# Smart_Extruder_Board.net
KiCad netlist of a schematic drawn in EAGLE
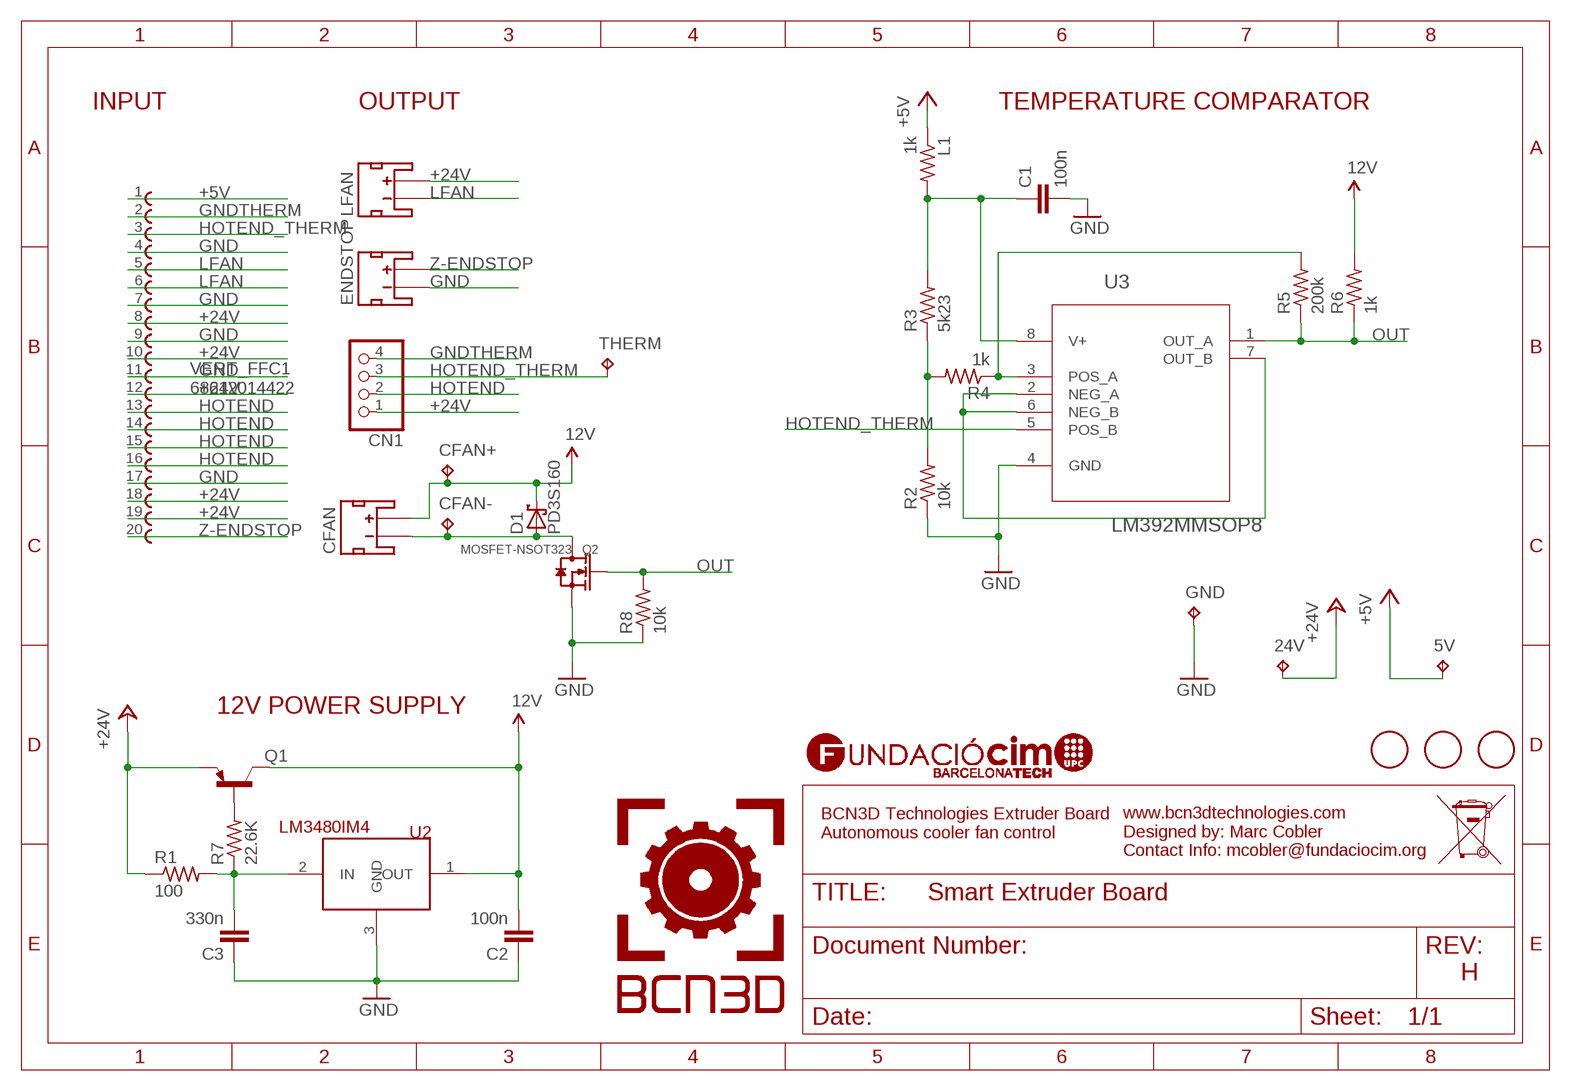
[diagram p0: schematic, sheet 1]

(export (version "E")
  (design (tool "Eeschema 10.0.6"))
  (components
    (comp (ref "5V")
      (value "TPB1,27")
      (footprint "eagle-import:B1,27")
      (libsource (lib "eagle-import") (part "TPB1,27"))
    )
    (comp (ref "24V")
      (value "TPB1,27")
      (footprint "eagle-import:B1,27")
      (libsource (lib "eagle-import") (part "TPB1,27"))
    )
    (comp (ref "C1")
      (value "100n")
      (footprint "eagle-import:C0603K")
      (fields (field (name "MF") "AVX") (field (name "MPN") "06035C104KAT2A"))
      (libsource (lib "eagle-import") (part "C-EUC0603K"))
    )
    (comp (ref "C2")
      (value "100n")
      (footprint "eagle-import:C0603K")
      (fields (field (name "MF") "AVX") (field (name "MPN") "06035C104KAT2A"))
      (libsource (lib "eagle-import") (part "C-EUC0603K"))
    )
    (comp (ref "C3")
      (value "330n")
      (footprint "eagle-import:C0805")
      (fields (field (name "MF") "MURATA") (field (name "MPN") "GRM219R71H334KA88D"))
      (libsource (lib "eagle-import") (part "C-EUC0805"))
    )
    (comp (ref "CFAN")
      (value "JST_2MM_MALE")
      (footprint "eagle-import:JST-2-SMD")
      (fields
        (field (name "MF") "JST (JAPAN SOLDERLESS TERMINALS)")
        (field (name "MPN") "S2B-PH-SM4-TB(LF)(SN)")
      )
      (libsource (lib "eagle-import") (part "JST_2MM_MALE"))
    )
    (comp (ref "CFAN+")
      (value "TPB1,27")
      (footprint "eagle-import:B1,27")
      (libsource (lib "eagle-import") (part "TPB1,27"))
    )
    (comp (ref "CFAN-")
      (value "TPB1,27")
      (footprint "eagle-import:B1,27")
      (libsource (lib "eagle-import") (part "TPB1,27"))
    )
    (comp (ref "CN1")
      (value "JST_4PINPA")
      (footprint "eagle-import:JST_PA_04")
      (fields
        (field (name "MF") "JST (JAPAN SOLDERLESS TERMINALS)")
        (field (name "MPN") "SM04B-PASS-TBT(LF)(SN)")
      )
      (libsource (lib "eagle-import") (part "JST_4PINPA"))
    )
    (comp (ref "D1")
      (value "PD3S160")
      (footprint "eagle-import:POWERDI323")
      (fields (field (name "MF") "DIODES INC.") (field (name "MPN") "PD3S160-7"))
      (libsource (lib "eagle-import") (part "PD3S160"))
    )
    (comp (ref "ENDSTOP")
      (value "JST_2MM_MALE")
      (footprint "eagle-import:JST-2-SMD")
      (fields
        (field (name "MF") "JST (JAPAN SOLDERLESS TERMINALS)")
        (field (name "MPN") "S2B-PH-SM4-TB(LF)(SN)")
      )
      (libsource (lib "eagle-import") (part "JST_2MM_MALE"))
    )
    (comp (ref "GND")
      (value "TPB1,27")
      (footprint "eagle-import:B1,27")
      (libsource (lib "eagle-import") (part "TPB1,27"))
    )
    (comp (ref "L1")
      (value "1k")
      (footprint "eagle-import:R0603")
      (fields (field (name "MF") "MULTICOMP") (field (name "MPN") "MCMR06X1001FTL"))
      (libsource (lib "eagle-import") (part "R-US_R0603"))
    )
    (comp (ref "LFAN")
      (value "JST_2MM_MALE")
      (footprint "eagle-import:JST-2-SMD")
      (fields
        (field (name "MF") "JST (JAPAN SOLDERLESS TERMINALS)")
        (field (name "MPN") "S2B-PH-SM4-TB(LF)(SN)")
      )
      (libsource (lib "eagle-import") (part "JST_2MM_MALE"))
    )
    (comp (ref "Q1")
      (value "BC807W")
      (footprint "eagle-import:SOT323-BEC")
      (fields (field (name "MF") "NXP") (field (name "MPN") "BC807W,115"))
      (libsource (lib "eagle-import") (part "BC807W"))
    )
    (comp (ref "Q2")
      (value "MOSFET-NSOT323")
      (footprint "eagle-import:SOT323")
      (fields (field (name "MF") "NXP") (field (name "MPN") "PMF370XN,115"))
      (libsource (lib "eagle-import") (part "MOSFET-NSOT323"))
    )
    (comp (ref "R1")
      (value "100")
      (footprint "eagle-import:R1210")
      (fields (field (name "MF") "MULTICOMP") (field (name "MPN") "MC0603SAF330JT5E"))
      (libsource (lib "eagle-import") (part "R-US_R1210"))
    )
    (comp (ref "R2")
      (value "10k")
      (footprint "eagle-import:R0603")
      (fields (field (name "MF") "MULTICOMP") (field (name "MPN") "MCMR06X1002FTL"))
      (libsource (lib "eagle-import") (part "R-US_R0603"))
    )
    (comp (ref "R3")
      (value "5k23")
      (footprint "eagle-import:R0603")
      (fields (field (name "MF") "PANASONIC ELECTRONIC COMPONENTS") (field (name "MPN") "ERJ3EKF5231V"))
      (libsource (lib "eagle-import") (part "R-US_R0603"))
    )
    (comp (ref "R4")
      (value "1k")
      (footprint "eagle-import:R0603")
      (fields (field (name "MF") "MULTICOMP") (field (name "MPN") "MCMR06X1001FTL"))
      (libsource (lib "eagle-import") (part "R-US_R0603"))
    )
    (comp (ref "R5")
      (value "200k")
      (footprint "eagle-import:R0603")
      (fields (field (name "MF") "PANASONIC ELECTRONIC COMPONENTS") (field (name "MPN") "ERJ3EKF2003V"))
      (libsource (lib "eagle-import") (part "R-US_R0603"))
    )
    (comp (ref "R6")
      (value "1k")
      (footprint "eagle-import:R0603")
      (fields (field (name "MF") "MULTICOMP") (field (name "MPN") "MCMR06X1001FTL"))
      (libsource (lib "eagle-import") (part "R-US_R0603"))
    )
    (comp (ref "R7")
      (value "22.6K")
      (footprint "eagle-import:R0603")
      (fields (field (name "MF") "MULTICOMP") (field (name "MPN") "MC0603SAF330JT5E"))
      (libsource (lib "eagle-import") (part "R-US_R0603"))
    )
    (comp (ref "R8")
      (value "10k")
      (footprint "eagle-import:R0603")
      (fields (field (name "MF") "MULTICOMP") (field (name "MPN") "MCMR06X1002FTL"))
      (libsource (lib "eagle-import") (part "R-US_R0603"))
    )
    (comp (ref "THERM")
      (value "TPB1,27")
      (footprint "eagle-import:B1,27")
      (libsource (lib "eagle-import") (part "TPB1,27"))
    )
    (comp (ref "U$1")
      (value "FIDUCIAL")
      (footprint "eagle-import:FIDUCIAL_1MM")
      (libsource (lib "eagle-import") (part "FIDUCIAL"))
    )
    (comp (ref "U$2")
      (value "FIDUCIAL")
      (footprint "eagle-import:FIDUCIAL_1MM")
      (libsource (lib "eagle-import") (part "FIDUCIAL"))
    )
    (comp (ref "U$3")
      (value "FIDUCIAL")
      (footprint "eagle-import:FIDUCIAL_1MM")
      (libsource (lib "eagle-import") (part "FIDUCIAL"))
    )
    (comp (ref "U2")
      (value "LM3480IM4")
      (footprint "eagle-import:SOT23-3")
      (fields (field (name "MF") "TEXAS INSTRUMENTS") (field (name "MPN") "LM3480IM3-12/NOPB"))
      (libsource (lib "eagle-import") (part "LM3480IM4"))
    )
    (comp (ref "U3")
      (value "LM392MMSOP8")
      (footprint "eagle-import:MSOP8")
      (libsource (lib "eagle-import") (part "LM392MMSOP8"))
    )
    (comp (ref "VERT_FFC1")
      (value "68612014422")
      (footprint "eagle-import:68612014422")
      (libsource (lib "eagle-import") (part "68612014422"))
    )
  )
  (nets
    (net (code "1") (name "+5V") (class "Default")
      (node (ref "5V") (pin "TP") (pinfunction "TP_TP") (pintype "input"))
      (node (ref "L1") (pin "1") (pinfunction "1_1") (pintype "passive"))
      (node (ref "VERT_FFC1") (pin "1") (pinfunction "1_1") (pintype "passive"))
    )
    (net (code "2") (name "+24V") (class "Default")
      (node (ref "24V") (pin "TP") (pinfunction "TP_TP") (pintype "input"))
      (node (ref "CN1") (pin "1") (pinfunction "1_1") (pintype "passive"))
      (node (ref "LFAN") (pin "2") (pinfunction "+_2") (pintype "bidirectional"))
      (node (ref "Q1") (pin "2") (pinfunction "E_2") (pintype "passive"))
      (node (ref "R1") (pin "1") (pinfunction "1_1") (pintype "passive"))
      (node (ref "VERT_FFC1") (pin "10") (pinfunction "10_10") (pintype "passive"))
      (node (ref "VERT_FFC1") (pin "12") (pinfunction "12_12") (pintype "passive"))
      (node (ref "VERT_FFC1") (pin "18") (pinfunction "18_18") (pintype "passive"))
      (node (ref "VERT_FFC1") (pin "19") (pinfunction "19_19") (pintype "passive"))
      (node (ref "VERT_FFC1") (pin "8") (pinfunction "8_8") (pintype "passive"))
    )
    (net (code "3") (name "/GNDTHERM") (class "Default")
      (node (ref "CN1") (pin "4") (pinfunction "4_4") (pintype "passive"))
      (node (ref "VERT_FFC1") (pin "2") (pinfunction "2_2") (pintype "passive"))
    )
    (net (code "4") (name "/HOTEND") (class "Default")
      (node (ref "CN1") (pin "2") (pinfunction "2_2") (pintype "passive"))
      (node (ref "VERT_FFC1") (pin "13") (pinfunction "13_13") (pintype "passive"))
      (node (ref "VERT_FFC1") (pin "14") (pinfunction "14_14") (pintype "passive"))
      (node (ref "VERT_FFC1") (pin "15") (pinfunction "15_15") (pintype "passive"))
      (node (ref "VERT_FFC1") (pin "16") (pinfunction "16_16") (pintype "passive"))
    )
    (net (code "5") (name "/HOTEND_THERM") (class "Default")
      (node (ref "CN1") (pin "3") (pinfunction "3_3") (pintype "passive"))
      (node (ref "THERM") (pin "TP") (pinfunction "TP_TP") (pintype "input"))
      (node (ref "U3") (pin "5") (pinfunction "POS_B_5") (pintype "input"))
      (node (ref "VERT_FFC1") (pin "3") (pinfunction "3_3") (pintype "passive"))
    )
    (net (code "6") (name "/LFAN") (class "Default")
      (node (ref "LFAN") (pin "1") (pinfunction "-_1") (pintype "bidirectional"))
      (node (ref "VERT_FFC1") (pin "5") (pinfunction "5_5") (pintype "passive"))
      (node (ref "VERT_FFC1") (pin "6") (pinfunction "6_6") (pintype "passive"))
    )
    (net (code "7") (name "/OUT") (class "Default")
      (node (ref "Q2") (pin "1") (pinfunction "G_1") (pintype "passive"))
      (node (ref "R5") (pin "1") (pinfunction "1_1") (pintype "passive"))
      (node (ref "R6") (pin "1") (pinfunction "1_1") (pintype "passive"))
      (node (ref "R8") (pin "2") (pinfunction "2_2") (pintype "passive"))
      (node (ref "U3") (pin "1") (pinfunction "OUT_A_1") (pintype "output"))
    )
    (net (code "8") (name "/Z-ENDSTOP") (class "Default")
      (node (ref "ENDSTOP") (pin "2") (pinfunction "+_2") (pintype "bidirectional"))
      (node (ref "VERT_FFC1") (pin "20") (pinfunction "20_20") (pintype "passive"))
    )
    (net (code "9") (name "12V") (class "Default")
      (node (ref "C2") (pin "2") (pinfunction "2_2") (pintype "passive"))
      (node (ref "CFAN") (pin "2") (pinfunction "+_2") (pintype "bidirectional"))
      (node (ref "CFAN+") (pin "TP") (pinfunction "TP_TP") (pintype "input"))
      (node (ref "D1") (pin "C") (pinfunction "C_C") (pintype "passive"))
      (node (ref "Q1") (pin "3") (pinfunction "C_3") (pintype "passive"))
      (node (ref "R6") (pin "2") (pinfunction "2_2") (pintype "passive"))
      (node (ref "U2") (pin "1") (pinfunction "OUT_1") (pintype "bidirectional"))
    )
    (net (code "10") (name "GND") (class "Default")
      (node (ref "C1") (pin "2") (pinfunction "2_2") (pintype "passive"))
      (node (ref "C2") (pin "1") (pinfunction "1_1") (pintype "passive"))
      (node (ref "C3") (pin "1") (pinfunction "1_1") (pintype "passive"))
      (node (ref "ENDSTOP") (pin "1") (pinfunction "-_1") (pintype "bidirectional"))
      (node (ref "GND") (pin "TP") (pinfunction "TP_TP") (pintype "input"))
      (node (ref "Q2") (pin "2") (pinfunction "S_2") (pintype "passive"))
      (node (ref "R2") (pin "1") (pinfunction "1_1") (pintype "passive"))
      (node (ref "R8") (pin "1") (pinfunction "1_1") (pintype "passive"))
      (node (ref "U2") (pin "3") (pinfunction "GND_3") (pintype "bidirectional"))
      (node (ref "U3") (pin "4") (pinfunction "GND_4") (pintype "passive"))
      (node (ref "VERT_FFC1") (pin "11") (pinfunction "11_11") (pintype "passive"))
      (node (ref "VERT_FFC1") (pin "17") (pinfunction "17_17") (pintype "passive"))
      (node (ref "VERT_FFC1") (pin "4") (pinfunction "4_4") (pintype "passive"))
      (node (ref "VERT_FFC1") (pin "7") (pinfunction "7_7") (pintype "passive"))
      (node (ref "VERT_FFC1") (pin "9") (pinfunction "9_9") (pintype "passive"))
    )
    (net (code "11") (name "Net-(CFAN--)") (class "Default")
      (node (ref "CFAN") (pin "1") (pinfunction "-_1") (pintype "bidirectional"))
      (node (ref "CFAN-") (pin "TP") (pinfunction "TP_TP") (pintype "input"))
      (node (ref "D1") (pin "A") (pinfunction "A_A") (pintype "passive"))
      (node (ref "Q2") (pin "3") (pinfunction "D_3") (pintype "passive"))
    )
    (net (code "12") (name "Net-(Q1-B)") (class "Default")
      (node (ref "Q1") (pin "1") (pinfunction "B_1") (pintype "passive"))
      (node (ref "R7") (pin "2") (pinfunction "2_2") (pintype "passive"))
    )
    (net (code "13") (name "Net-(R2-Pad2)") (class "Default")
      (node (ref "R2") (pin "2") (pinfunction "2_2") (pintype "passive"))
      (node (ref "R3") (pin "1") (pinfunction "1_1") (pintype "passive"))
      (node (ref "R4") (pin "2") (pinfunction "2_2") (pintype "passive"))
    )
    (net (code "14") (name "Net-(U2-IN)") (class "Default")
      (node (ref "C3") (pin "2") (pinfunction "2_2") (pintype "passive"))
      (node (ref "R1") (pin "2") (pinfunction "2_2") (pintype "passive"))
      (node (ref "R7") (pin "1") (pinfunction "1_1") (pintype "passive"))
      (node (ref "U2") (pin "2") (pinfunction "IN_2") (pintype "bidirectional"))
    )
    (net (code "15") (name "Net-(U3-NEG_A)") (class "Default")
      (node (ref "U3") (pin "2") (pinfunction "NEG_A_2") (pintype "input"))
      (node (ref "U3") (pin "6") (pinfunction "NEG_B_6") (pintype "input"))
      (node (ref "U3") (pin "7") (pinfunction "OUT_B_7") (pintype "output"))
    )
    (net (code "16") (name "Net-(U3-POS_A)") (class "Default")
      (node (ref "R4") (pin "1") (pinfunction "1_1") (pintype "passive"))
      (node (ref "R5") (pin "2") (pinfunction "2_2") (pintype "passive"))
      (node (ref "U3") (pin "3") (pinfunction "POS_A_3") (pintype "input"))
    )
    (net (code "17") (name "Net-(U3-V+)") (class "Default")
      (node (ref "C1") (pin "1") (pinfunction "1_1") (pintype "passive"))
      (node (ref "L1") (pin "2") (pinfunction "2_2") (pintype "passive"))
      (node (ref "R3") (pin "2") (pinfunction "2_2") (pintype "passive"))
      (node (ref "U3") (pin "8") (pinfunction "V+_8") (pintype "power_in"))
    )
    (net (code "18") (name "unconnected-(CFAN-PAD1-PadNC1)") (class "Default")
      (node (ref "CFAN") (pin "NC1") (pinfunction "PAD1_NC1") (pintype "bidirectional"))
    )
    (net (code "19") (name "unconnected-(CFAN-PAD2-PadNC2)") (class "Default")
      (node (ref "CFAN") (pin "NC2") (pinfunction "PAD2_NC2") (pintype "bidirectional"))
    )
    (net (code "20") (name "unconnected-(ENDSTOP-PAD1-PadNC1)") (class "Default")
      (node (ref "ENDSTOP") (pin "NC1") (pinfunction "PAD1_NC1") (pintype "bidirectional"))
    )
    (net (code "21") (name "unconnected-(ENDSTOP-PAD2-PadNC2)") (class "Default")
      (node (ref "ENDSTOP") (pin "NC2") (pinfunction "PAD2_NC2") (pintype "bidirectional"))
    )
    (net (code "22") (name "unconnected-(LFAN-PAD1-PadNC1)") (class "Default")
      (node (ref "LFAN") (pin "NC1") (pinfunction "PAD1_NC1") (pintype "bidirectional"))
    )
    (net (code "23") (name "unconnected-(LFAN-PAD2-PadNC2)") (class "Default")
      (node (ref "LFAN") (pin "NC2") (pinfunction "PAD2_NC2") (pintype "bidirectional"))
    )
  )
)
